# User_Interface.net
KiCad netlist of a schematic drawn in Altium Designer
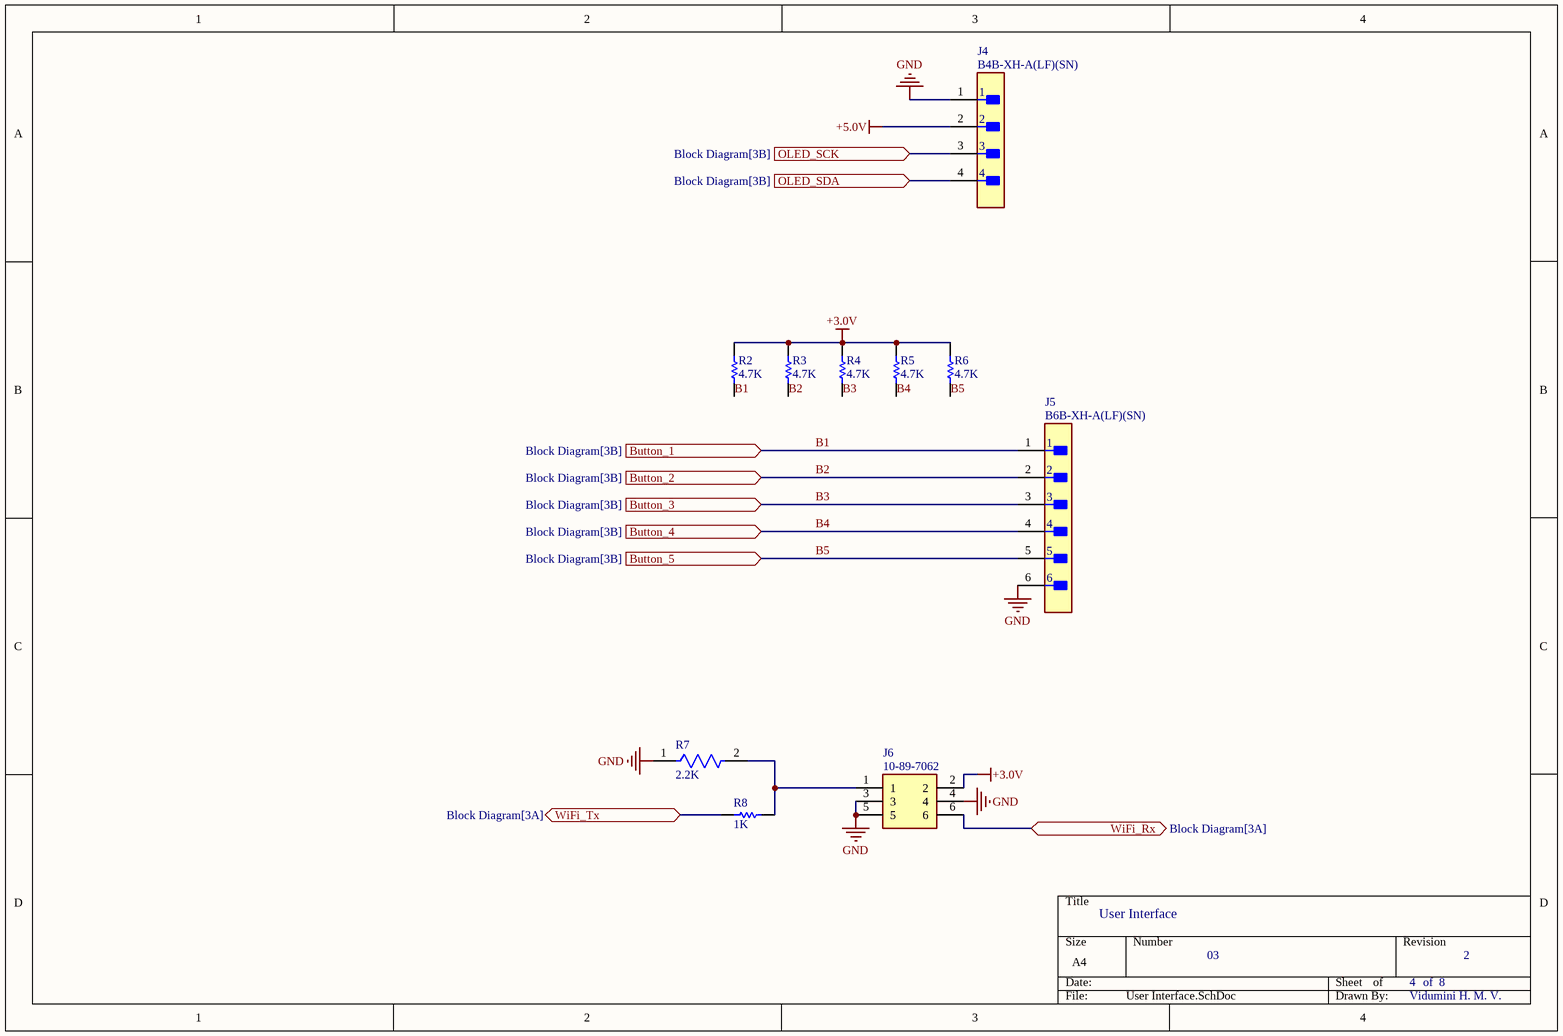
[diagram p0: User Interface.SchDoc]

(export (version "E")
  (design (tool "Eeschema 10.0.6"))
  (components
    (comp (ref "J4")
      (value "B4B-XH-A(LF)(SN)")
      (footprint "FP-B4B-XH-A_LF_SN-MFG")
      (description "CONN HEADER VERT 4POS 2.5MM")
      (libsource (lib "Altium Content Vault") (part "299a8cea1bdcbc3624fe62c390fa72c"))
    )
    (comp (ref "J5")
      (value "B6B-XH-A(LF)(SN)")
      (footprint "FP-B6B-XH-A_LF_SN-MFG")
      (description "CONN HEADER VERT 6POS 2.5MM")
      (libsource (lib "Altium Content Vault") (part "f2cb566baf1c37ab5a3b8e90bbeafd6"))
    )
    (comp (ref "J6")
      (value "10-89-7062")
      (footprint "SamacSys:HDRV6W87P254_2X3_775X508X864P")
      (description "Connector")
      (fields (field (name "MOUSER PART NUMBER") "538-10-89-7062"))
      (libsource (lib "*") (part "10-89-7062"))
    )
    (comp (ref "R2")
      (value "4.7K")
      (footprint "RESC3216X60X45ML15T20")
      (description "Chip Resistor, 4.7 KOhm, +/- 1%, 0.25 W, -55 to 155 degC, 1206 (3216 Metric), RoHS, Tape and Reel")
      (fields (field (name "MANUFACTURER") "Vishay Semiconductor") (field (name "TOLERANCE") "1%"))
      (libsource (lib "Altium Content Vault") (part "RES-2"))
    )
    (comp (ref "R3")
      (value "4.7K")
      (footprint "RESC3216X60X45ML15T20")
      (description "Chip Resistor, 4.7 KOhm, +/- 1%, 0.25 W, -55 to 155 degC, 1206 (3216 Metric), RoHS, Tape and Reel")
      (fields (field (name "MANUFACTURER") "Vishay Semiconductor") (field (name "TOLERANCE") "1%"))
      (libsource (lib "Altium Content Vault") (part "RES-2"))
    )
    (comp (ref "R4")
      (value "4.7K")
      (footprint "RESC3216X60X45ML15T20")
      (description "Chip Resistor, 4.7 KOhm, +/- 1%, 0.25 W, -55 to 155 degC, 1206 (3216 Metric), RoHS, Tape and Reel")
      (fields (field (name "MANUFACTURER") "Vishay Semiconductor") (field (name "TOLERANCE") "1%"))
      (libsource (lib "Altium Content Vault") (part "RES-2"))
    )
    (comp (ref "R5")
      (value "4.7K")
      (footprint "RESC3216X60X45ML15T20")
      (description "Chip Resistor, 4.7 KOhm, +/- 1%, 0.25 W, -55 to 155 degC, 1206 (3216 Metric), RoHS, Tape and Reel")
      (fields (field (name "MANUFACTURER") "Vishay Semiconductor") (field (name "TOLERANCE") "1%"))
      (libsource (lib "Altium Content Vault") (part "RES-2"))
    )
    (comp (ref "R6")
      (value "4.7K")
      (footprint "RESC3216X60X45ML15T20")
      (description "Chip Resistor, 4.7 KOhm, +/- 1%, 0.25 W, -55 to 155 degC, 1206 (3216 Metric), RoHS, Tape and Reel")
      (fields (field (name "MANUFACTURER") "Vishay Semiconductor") (field (name "TOLERANCE") "1%"))
      (libsource (lib "Altium Content Vault") (part "RES-2"))
    )
    (comp (ref "R7")
      (value "2.2K")
      (footprint "FP-RT1206-MFG")
      (description "RES 2.20K OHM 1/4W .1% SMD 1206")
      (fields (field (name "MANUFACTURER PART NUMBER") "RT1206BRD072K2L") (field (name "TOLERANCE") "0.005"))
      (libsource (lib "Altium Content Vault") (part "1029c3af85768c4190bb7ad29bc67b5"))
    )
    (comp (ref "R8")
      (value "1K")
      (footprint "RESC3116X65X40ML10T20")
      (description "Chip Resistor, 1 KOhm, +/- 1%, 0.25 W, -55 to 155 degC, 1206 (3216 Metric), RoHS, Tape and Reel")
      (fields (field (name "TOLERANCE") "1%") (field (name "MANUFACTURER") "Yageo"))
      (libsource (lib "Altium Content Vault") (part "RES-2"))
    )
  )
  (nets
    (net (code "1") (name "+3.0V") (class "Default")
      (node (ref "J6") (pin "2") (pinfunction "2_2") (pintype "passive"))
      (node (ref "R2") (pin "1") (pinfunction "1_1") (pintype "passive"))
      (node (ref "R3") (pin "1") (pinfunction "1_1") (pintype "passive"))
      (node (ref "R4") (pin "1") (pinfunction "1_1") (pintype "passive"))
      (node (ref "R5") (pin "1") (pinfunction "1_1") (pintype "passive"))
      (node (ref "R6") (pin "1") (pinfunction "1_1") (pintype "passive"))
    )
    (net (code "2") (name "+5.0V") (class "Default")
      (node (ref "J4") (pin "2") (pinfunction "2_2") (pintype "passive"))
    )
    (net (code "3") (name "/B1") (class "Default")
      (node (ref "J5") (pin "1") (pinfunction "1_1") (pintype "passive"))
      (node (ref "R2") (pin "2") (pinfunction "2_2") (pintype "passive"))
    )
    (net (code "4") (name "/B2") (class "Default")
      (node (ref "J5") (pin "2") (pinfunction "2_2") (pintype "passive"))
      (node (ref "R3") (pin "2") (pinfunction "2_2") (pintype "passive"))
    )
    (net (code "5") (name "/B3") (class "Default")
      (node (ref "J5") (pin "3") (pinfunction "3_3") (pintype "passive"))
      (node (ref "R4") (pin "2") (pinfunction "2_2") (pintype "passive"))
    )
    (net (code "6") (name "/B4") (class "Default")
      (node (ref "J5") (pin "4") (pinfunction "4_4") (pintype "passive"))
      (node (ref "R5") (pin "2") (pinfunction "2_2") (pintype "passive"))
    )
    (net (code "7") (name "/B5") (class "Default")
      (node (ref "J5") (pin "5") (pinfunction "5_5") (pintype "passive"))
      (node (ref "R6") (pin "2") (pinfunction "2_2") (pintype "passive"))
    )
    (net (code "8") (name "/OLED_SCK") (class "Default")
      (node (ref "J4") (pin "3") (pinfunction "3_3") (pintype "passive"))
    )
    (net (code "9") (name "/OLED_SDA") (class "Default")
      (node (ref "J4") (pin "4") (pinfunction "4_4") (pintype "passive"))
    )
    (net (code "10") (name "/WiFi_Rx") (class "Default")
      (node (ref "J6") (pin "6") (pinfunction "6_6") (pintype "passive"))
    )
    (net (code "11") (name "/WiFi_Tx") (class "Default")
      (node (ref "R8") (pin "1") (pinfunction "1_1") (pintype "passive"))
    )
    (net (code "12") (name "GND") (class "Default")
      (node (ref "J4") (pin "1") (pinfunction "1_1") (pintype "passive"))
      (node (ref "J5") (pin "6") (pinfunction "6_6") (pintype "passive"))
      (node (ref "J6") (pin "3") (pinfunction "3_3") (pintype "passive"))
      (node (ref "J6") (pin "4") (pinfunction "4_4") (pintype "passive"))
      (node (ref "J6") (pin "5") (pinfunction "5_5") (pintype "passive"))
      (node (ref "R7") (pin "1") (pinfunction "1_1") (pintype "passive"))
    )
    (net (code "13") (name "Net-(J6-Pad1)") (class "Default")
      (node (ref "J6") (pin "1") (pinfunction "1_1") (pintype "passive"))
      (node (ref "R7") (pin "2") (pinfunction "2_2") (pintype "passive"))
      (node (ref "R8") (pin "2") (pinfunction "2_2") (pintype "passive"))
    )
  )
)
